# 1593K-WirelessTallyReceiver-XBee.net
KiCad netlist of a schematic drawn in EAGLE
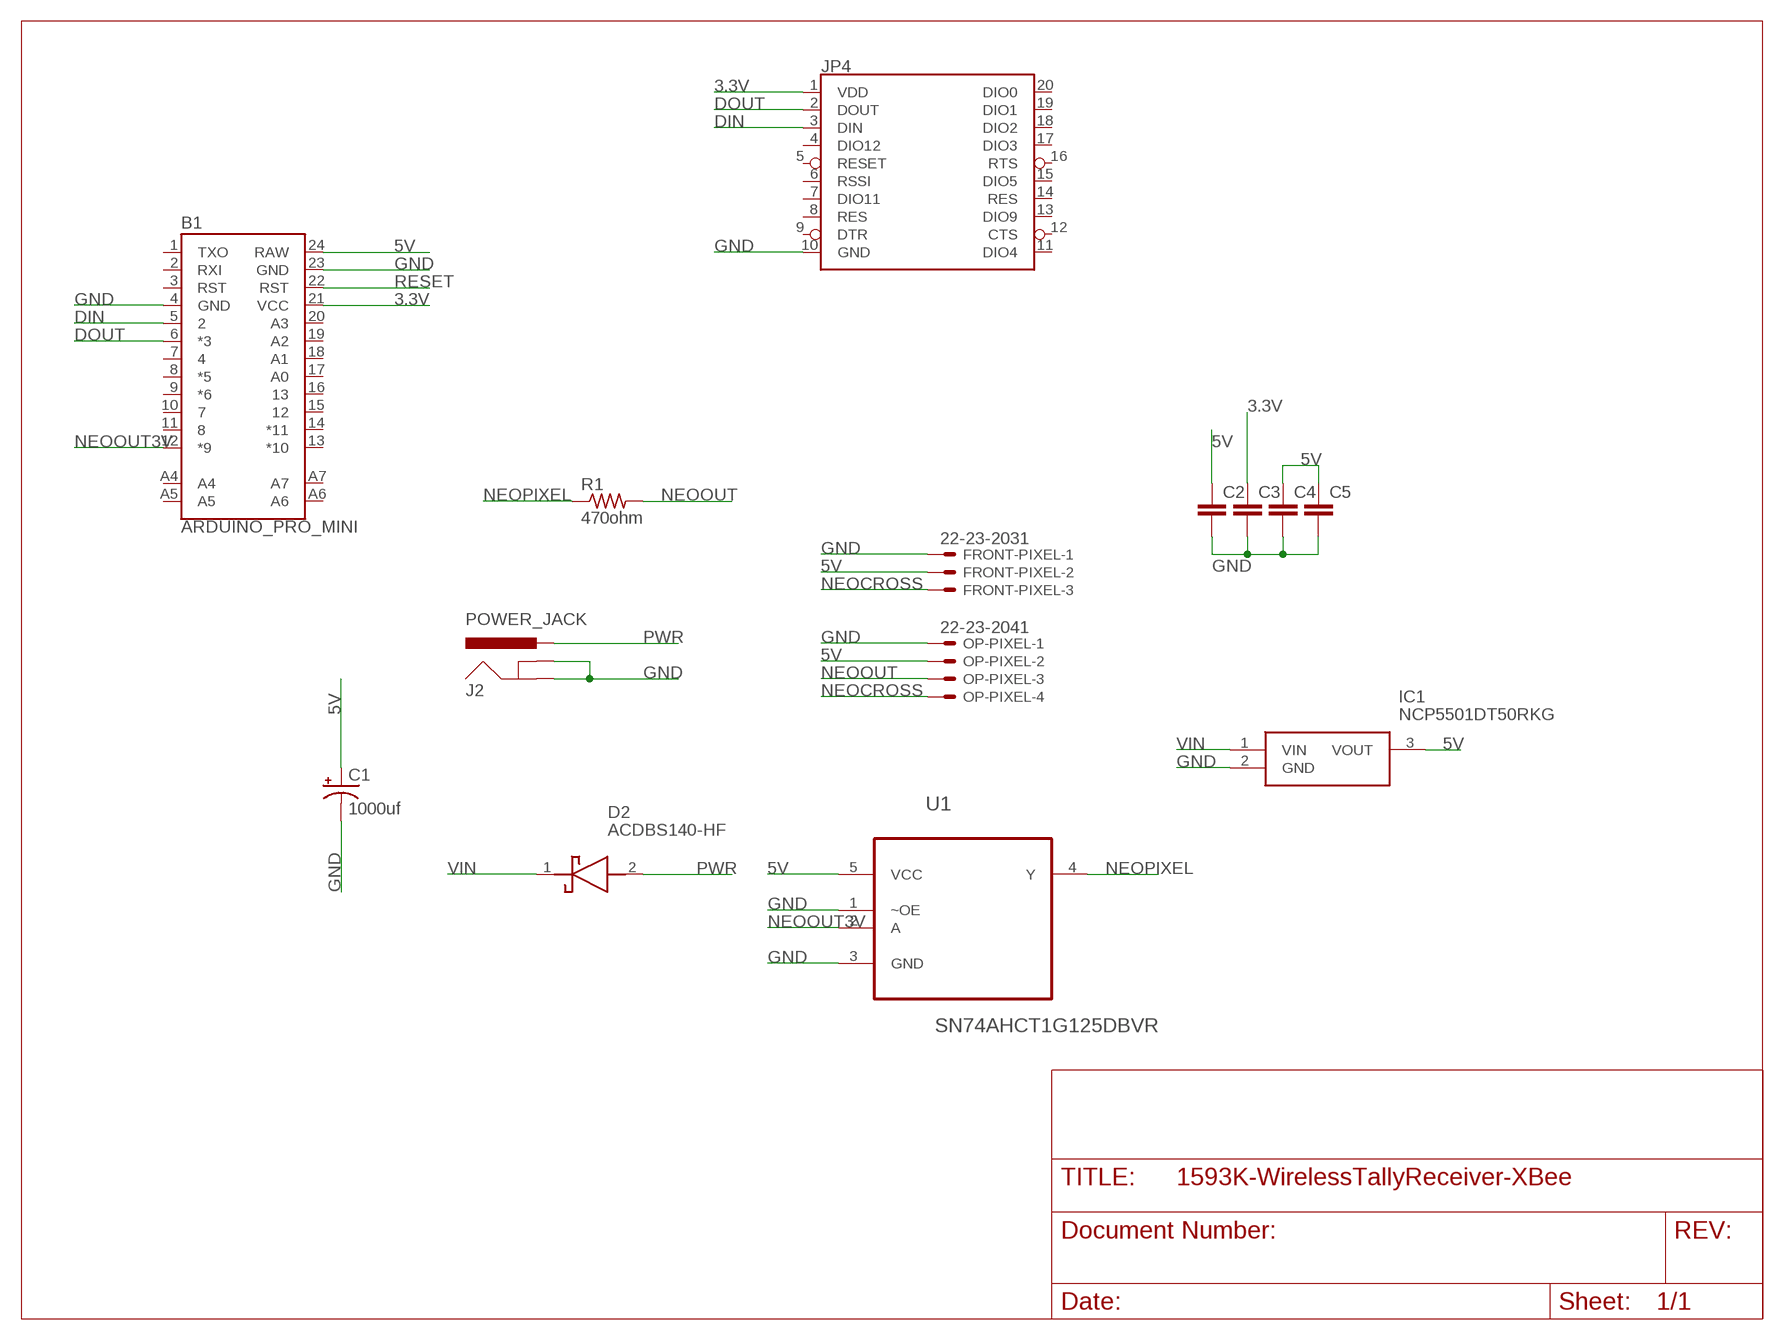
[diagram p0: schematic, sheet 1]

(export (version "E")
  (design (tool "Eeschema 10.0.6"))
  (components
    (comp (ref "B1")
      (value "ARDUINO_PRO_MINI")
      (footprint "eagle-import:ARDUINO_PRO_MINI")
      (libsource (lib "eagle-import") (part "ARDUINO_PRO_MINI"))
    )
    (comp (ref "C1")
      (value "1000uf")
      (footprint "eagle-import:CPOL-RADIAL-5MM-10MM")
      (libsource (lib "eagle-import") (part "1000UF-RADIAL-5MM-25V-20%"))
    )
    (comp (ref "C2")
      (value "CAPACITOR_0805_N")
      (footprint "eagle-import:RESC0805_N")
      (libsource (lib "eagle-import") (part "CAPACITOR_0805_N"))
    )
    (comp (ref "C3")
      (value "CAPACITOR_0805_N")
      (footprint "eagle-import:RESC0805_N")
      (libsource (lib "eagle-import") (part "CAPACITOR_0805_N"))
    )
    (comp (ref "C4")
      (value "CAPACITOR_0805_N")
      (footprint "eagle-import:RESC0805_N")
      (libsource (lib "eagle-import") (part "CAPACITOR_0805_N"))
    )
    (comp (ref "C5")
      (value "CAPACITOR_0805_N")
      (footprint "eagle-import:RESC0805_N")
      (libsource (lib "eagle-import") (part "CAPACITOR_0805_N"))
    )
    (comp (ref "D2")
      (value "ACDBS140-HF")
      (footprint "eagle-import:DIOM2013X100N")
      (fields (field (name "MOUSER_PART_NUMBER") "750-ACDBS140-HF"))
      (libsource (lib "eagle-import") (part "ACDBS140-HF"))
    )
    (comp (ref "FRONT-PIXEL")
      (value "22-23-2031")
      (footprint "eagle-import:22-23-2031")
      (fields (field (name "MF") "MOLEX"))
      (libsource (lib "eagle-import") (part "22-23-2031"))
    )
    (comp (ref "IC1")
      (value "NCP5501DT50RKG")
      (footprint "eagle-import:NCP5501DT50RKG")
      (fields (field (name "MOUSER_PART_NUMBER") "863-NCP5501DT50RKG"))
      (libsource (lib "eagle-import") (part "NCP5501DT50RKG"))
    )
    (comp (ref "J2")
      (value "POWER_JACK")
      (footprint "eagle-import:POWER_JACK_PTH")
      (libsource (lib "eagle-import") (part "POWER_JACK"))
    )
    (comp (ref "JP4")
      (value "XBEESILK")
      (footprint "eagle-import:XBEE-SILK")
      (libsource (lib "eagle-import") (part "XBEESILK"))
    )
    (comp (ref "OP-PIXEL")
      (value "22-23-2041")
      (footprint "eagle-import:22-23-2041")
      (fields (field (name "MF") "MOLEX"))
      (libsource (lib "eagle-import") (part "22-23-2041"))
    )
    (comp (ref "R1")
      (value "470ohm")
      (footprint "eagle-import:R0805")
      (libsource (lib "eagle-import") (part "R-US_R0805"))
    )
    (comp (ref "U1")
      (value "SN74AHCT1G125DBVR")
      (footprint "eagle-import:SOT95P280X145-5N")
      (libsource (lib "eagle-import") (part "SN74AHCT1G125DBVR"))
    )
  )
  (nets
    (net (code "1") (name "/3.3V") (class "Default")
      (node (ref "B1") (pin "21") (pinfunction "VCC_21") (pintype "power_in"))
      (node (ref "C3") (pin "1") (pinfunction "1_1") (pintype "passive"))
      (node (ref "JP4") (pin "1") (pinfunction "VDD_1") (pintype "power_in"))
    )
    (net (code "2") (name "/5V") (class "Default")
      (node (ref "B1") (pin "24") (pinfunction "RAW_24") (pintype "power_in"))
      (node (ref "C1") (pin "+") (pinfunction "+_+") (pintype "passive"))
      (node (ref "C2") (pin "1") (pinfunction "1_1") (pintype "passive"))
      (node (ref "C4") (pin "1") (pinfunction "1_1") (pintype "passive"))
      (node (ref "C5") (pin "1") (pinfunction "1_1") (pintype "passive"))
      (node (ref "FRONT-PIXEL") (pin "2") (pinfunction "S_2") (pintype "passive"))
      (node (ref "IC1") (pin "3") (pinfunction "VOUT_3") (pintype "bidirectional"))
      (node (ref "OP-PIXEL") (pin "2") (pinfunction "S_2") (pintype "passive"))
      (node (ref "U1") (pin "5") (pinfunction "VCC_5") (pintype "power_in"))
    )
    (net (code "3") (name "/DIN") (class "Default")
      (node (ref "B1") (pin "5") (pinfunction "2_5") (pintype "bidirectional"))
      (node (ref "JP4") (pin "3") (pinfunction "DIN_3") (pintype "input"))
    )
    (net (code "4") (name "/DOUT") (class "Default")
      (node (ref "B1") (pin "6") (pinfunction "*3_6") (pintype "bidirectional"))
      (node (ref "JP4") (pin "2") (pinfunction "DOUT_2") (pintype "output"))
    )
    (net (code "5") (name "/GND") (class "Default")
      (node (ref "B1") (pin "23") (pinfunction "GND_23") (pintype "power_in"))
      (node (ref "B1") (pin "4") (pinfunction "GND_4") (pintype "power_in"))
      (node (ref "C1") (pin "-") (pinfunction "-_-") (pintype "passive"))
      (node (ref "C2") (pin "2") (pinfunction "2_2") (pintype "passive"))
      (node (ref "C3") (pin "2") (pinfunction "2_2") (pintype "passive"))
      (node (ref "C4") (pin "2") (pinfunction "2_2") (pintype "passive"))
      (node (ref "C5") (pin "2") (pinfunction "2_2") (pintype "passive"))
      (node (ref "FRONT-PIXEL") (pin "1") (pinfunction "S_1") (pintype "passive"))
      (node (ref "IC1") (pin "2") (pinfunction "GND_2") (pintype "bidirectional"))
      (node (ref "J2") (pin "GND") (pinfunction "GND_GND") (pintype "bidirectional"))
      (node (ref "J2") (pin "GNDBREAK") (pinfunction "GNDBREAK_GNDBREAK") (pintype "bidirectional"))
      (node (ref "JP4") (pin "10") (pinfunction "GND_10") (pintype "power_in"))
      (node (ref "OP-PIXEL") (pin "1") (pinfunction "S_1") (pintype "passive"))
      (node (ref "U1") (pin "1") (pinfunction "~{OE}_1") (pintype "input"))
      (node (ref "U1") (pin "3") (pinfunction "GND_3") (pintype "passive"))
    )
    (net (code "6") (name "/NEOCROSS") (class "Default")
      (node (ref "FRONT-PIXEL") (pin "3") (pinfunction "S_3") (pintype "passive"))
      (node (ref "OP-PIXEL") (pin "4") (pinfunction "S_4") (pintype "passive"))
    )
    (net (code "7") (name "/NEOOUT") (class "Default")
      (node (ref "OP-PIXEL") (pin "3") (pinfunction "S_3") (pintype "passive"))
      (node (ref "R1") (pin "2") (pinfunction "2_2") (pintype "passive"))
    )
    (net (code "8") (name "/NEOOUT3V") (class "Default")
      (node (ref "B1") (pin "12") (pinfunction "*9_12") (pintype "bidirectional"))
      (node (ref "U1") (pin "2") (pinfunction "A_2") (pintype "input"))
    )
    (net (code "9") (name "/NEOPIXEL") (class "Default")
      (node (ref "R1") (pin "1") (pinfunction "1_1") (pintype "passive"))
      (node (ref "U1") (pin "4") (pinfunction "Y_4") (pintype "output"))
    )
    (net (code "10") (name "/PWR") (class "Default")
      (node (ref "D2") (pin "2") (pinfunction "A_2") (pintype "bidirectional"))
      (node (ref "J2") (pin "PWR") (pinfunction "PWR_PWR") (pintype "bidirectional"))
    )
    (net (code "11") (name "/RESET") (class "Default")
      (node (ref "B1") (pin "22") (pinfunction "RST_22") (pintype "bidirectional"))
    )
    (net (code "12") (name "/VIN") (class "Default")
      (node (ref "D2") (pin "1") (pinfunction "K_1") (pintype "bidirectional"))
      (node (ref "IC1") (pin "1") (pinfunction "VIN_1") (pintype "bidirectional"))
    )
    (net (code "13") (name "unconnected-(B1-*5-Pad8)") (class "Default")
      (node (ref "B1") (pin "8") (pinfunction "*5_8") (pintype "bidirectional"))
    )
    (net (code "14") (name "unconnected-(B1-*6-Pad9)") (class "Default")
      (node (ref "B1") (pin "9") (pinfunction "*6_9") (pintype "bidirectional"))
    )
    (net (code "15") (name "unconnected-(B1-*10-Pad13)") (class "Default")
      (node (ref "B1") (pin "13") (pinfunction "*10_13") (pintype "bidirectional"))
    )
    (net (code "16") (name "unconnected-(B1-*11-Pad14)") (class "Default")
      (node (ref "B1") (pin "14") (pinfunction "*11_14") (pintype "bidirectional"))
    )
    (net (code "17") (name "unconnected-(B1-4-Pad7)") (class "Default")
      (node (ref "B1") (pin "7") (pinfunction "4_7") (pintype "bidirectional"))
    )
    (net (code "18") (name "unconnected-(B1-7-Pad10)") (class "Default")
      (node (ref "B1") (pin "10") (pinfunction "7_10") (pintype "bidirectional"))
    )
    (net (code "19") (name "unconnected-(B1-8-Pad11)") (class "Default")
      (node (ref "B1") (pin "11") (pinfunction "8_11") (pintype "bidirectional"))
    )
    (net (code "20") (name "unconnected-(B1-12-Pad15)") (class "Default")
      (node (ref "B1") (pin "15") (pinfunction "12_15") (pintype "bidirectional"))
    )
    (net (code "21") (name "unconnected-(B1-13-Pad16)") (class "Default")
      (node (ref "B1") (pin "16") (pinfunction "13_16") (pintype "bidirectional"))
    )
    (net (code "22") (name "unconnected-(B1-A0-Pad17)") (class "Default")
      (node (ref "B1") (pin "17") (pinfunction "A0_17") (pintype "bidirectional"))
    )
    (net (code "23") (name "unconnected-(B1-A1-Pad18)") (class "Default")
      (node (ref "B1") (pin "18") (pinfunction "A1_18") (pintype "bidirectional"))
    )
    (net (code "24") (name "unconnected-(B1-A2-Pad19)") (class "Default")
      (node (ref "B1") (pin "19") (pinfunction "A2_19") (pintype "bidirectional"))
    )
    (net (code "25") (name "unconnected-(B1-A3-Pad20)") (class "Default")
      (node (ref "B1") (pin "20") (pinfunction "A3_20") (pintype "bidirectional"))
    )
    (net (code "26") (name "unconnected-(B1-PadA4)") (class "Default")
      (node (ref "B1") (pin "A4") (pinfunction "A4_A4") (pintype "bidirectional"))
    )
    (net (code "27") (name "unconnected-(B1-PadA5)") (class "Default")
      (node (ref "B1") (pin "A5") (pinfunction "A5_A5") (pintype "bidirectional"))
    )
    (net (code "28") (name "unconnected-(B1-PadA6)") (class "Default")
      (node (ref "B1") (pin "A6") (pinfunction "A6_A6") (pintype "bidirectional"))
    )
    (net (code "29") (name "unconnected-(B1-PadA7)") (class "Default")
      (node (ref "B1") (pin "A7") (pinfunction "A7_A7") (pintype "bidirectional"))
    )
    (net (code "30") (name "unconnected-(B1-RST-Pad3)") (class "Default")
      (node (ref "B1") (pin "3") (pinfunction "RST_3") (pintype "bidirectional"))
    )
    (net (code "31") (name "unconnected-(B1-RXI-Pad2)") (class "Default")
      (node (ref "B1") (pin "2") (pinfunction "RXI_2") (pintype "bidirectional"))
    )
    (net (code "32") (name "unconnected-(B1-TXO-Pad1)") (class "Default")
      (node (ref "B1") (pin "1") (pinfunction "TXO_1") (pintype "bidirectional"))
    )
    (net (code "33") (name "unconnected-(JP4-CTS-Pad12)") (class "Default")
      (node (ref "JP4") (pin "12") (pinfunction "CTS_12") (pintype "output"))
    )
    (net (code "34") (name "unconnected-(JP4-DIO0-Pad20)") (class "Default")
      (node (ref "JP4") (pin "20") (pinfunction "DIO0_20") (pintype "bidirectional"))
    )
    (net (code "35") (name "unconnected-(JP4-DIO1-Pad19)") (class "Default")
      (node (ref "JP4") (pin "19") (pinfunction "DIO1_19") (pintype "bidirectional"))
    )
    (net (code "36") (name "unconnected-(JP4-DIO2-Pad18)") (class "Default")
      (node (ref "JP4") (pin "18") (pinfunction "DIO2_18") (pintype "bidirectional"))
    )
    (net (code "37") (name "unconnected-(JP4-DIO3-Pad17)") (class "Default")
      (node (ref "JP4") (pin "17") (pinfunction "DIO3_17") (pintype "bidirectional"))
    )
    (net (code "38") (name "unconnected-(JP4-DIO4-Pad11)") (class "Default")
      (node (ref "JP4") (pin "11") (pinfunction "DIO4_11") (pintype "bidirectional"))
    )
    (net (code "39") (name "unconnected-(JP4-DIO5-Pad15)") (class "Default")
      (node (ref "JP4") (pin "15") (pinfunction "DIO5_15") (pintype "bidirectional"))
    )
    (net (code "40") (name "unconnected-(JP4-DIO9-Pad13)") (class "Default")
      (node (ref "JP4") (pin "13") (pinfunction "DIO9_13") (pintype "bidirectional"))
    )
    (net (code "41") (name "unconnected-(JP4-DIO11-Pad7)") (class "Default")
      (node (ref "JP4") (pin "7") (pinfunction "DIO11_7") (pintype "bidirectional"))
    )
    (net (code "42") (name "unconnected-(JP4-DIO12-Pad4)") (class "Default")
      (node (ref "JP4") (pin "4") (pinfunction "DIO12_4") (pintype "bidirectional"))
    )
    (net (code "43") (name "unconnected-(JP4-DTR-Pad9)") (class "Default")
      (node (ref "JP4") (pin "9") (pinfunction "DTR_9") (pintype "bidirectional"))
    )
    (net (code "44") (name "unconnected-(JP4-RES-Pad8)") (class "Default")
      (node (ref "JP4") (pin "8") (pinfunction "RES_8") (pintype "bidirectional"))
    )
    (net (code "45") (name "unconnected-(JP4-RES-Pad14)") (class "Default")
      (node (ref "JP4") (pin "14") (pinfunction "RES_14") (pintype "bidirectional"))
    )
    (net (code "46") (name "unconnected-(JP4-RESET-Pad5)") (class "Default")
      (node (ref "JP4") (pin "5") (pinfunction "RESET_5") (pintype "input"))
    )
    (net (code "47") (name "unconnected-(JP4-RSSI-Pad6)") (class "Default")
      (node (ref "JP4") (pin "6") (pinfunction "RSSI_6") (pintype "bidirectional"))
    )
    (net (code "48") (name "unconnected-(JP4-RTS-Pad16)") (class "Default")
      (node (ref "JP4") (pin "16") (pinfunction "RTS_16") (pintype "input"))
    )
  )
)
